# Sheet2.net
KiCad netlist of a schematic drawn in Altium Designer
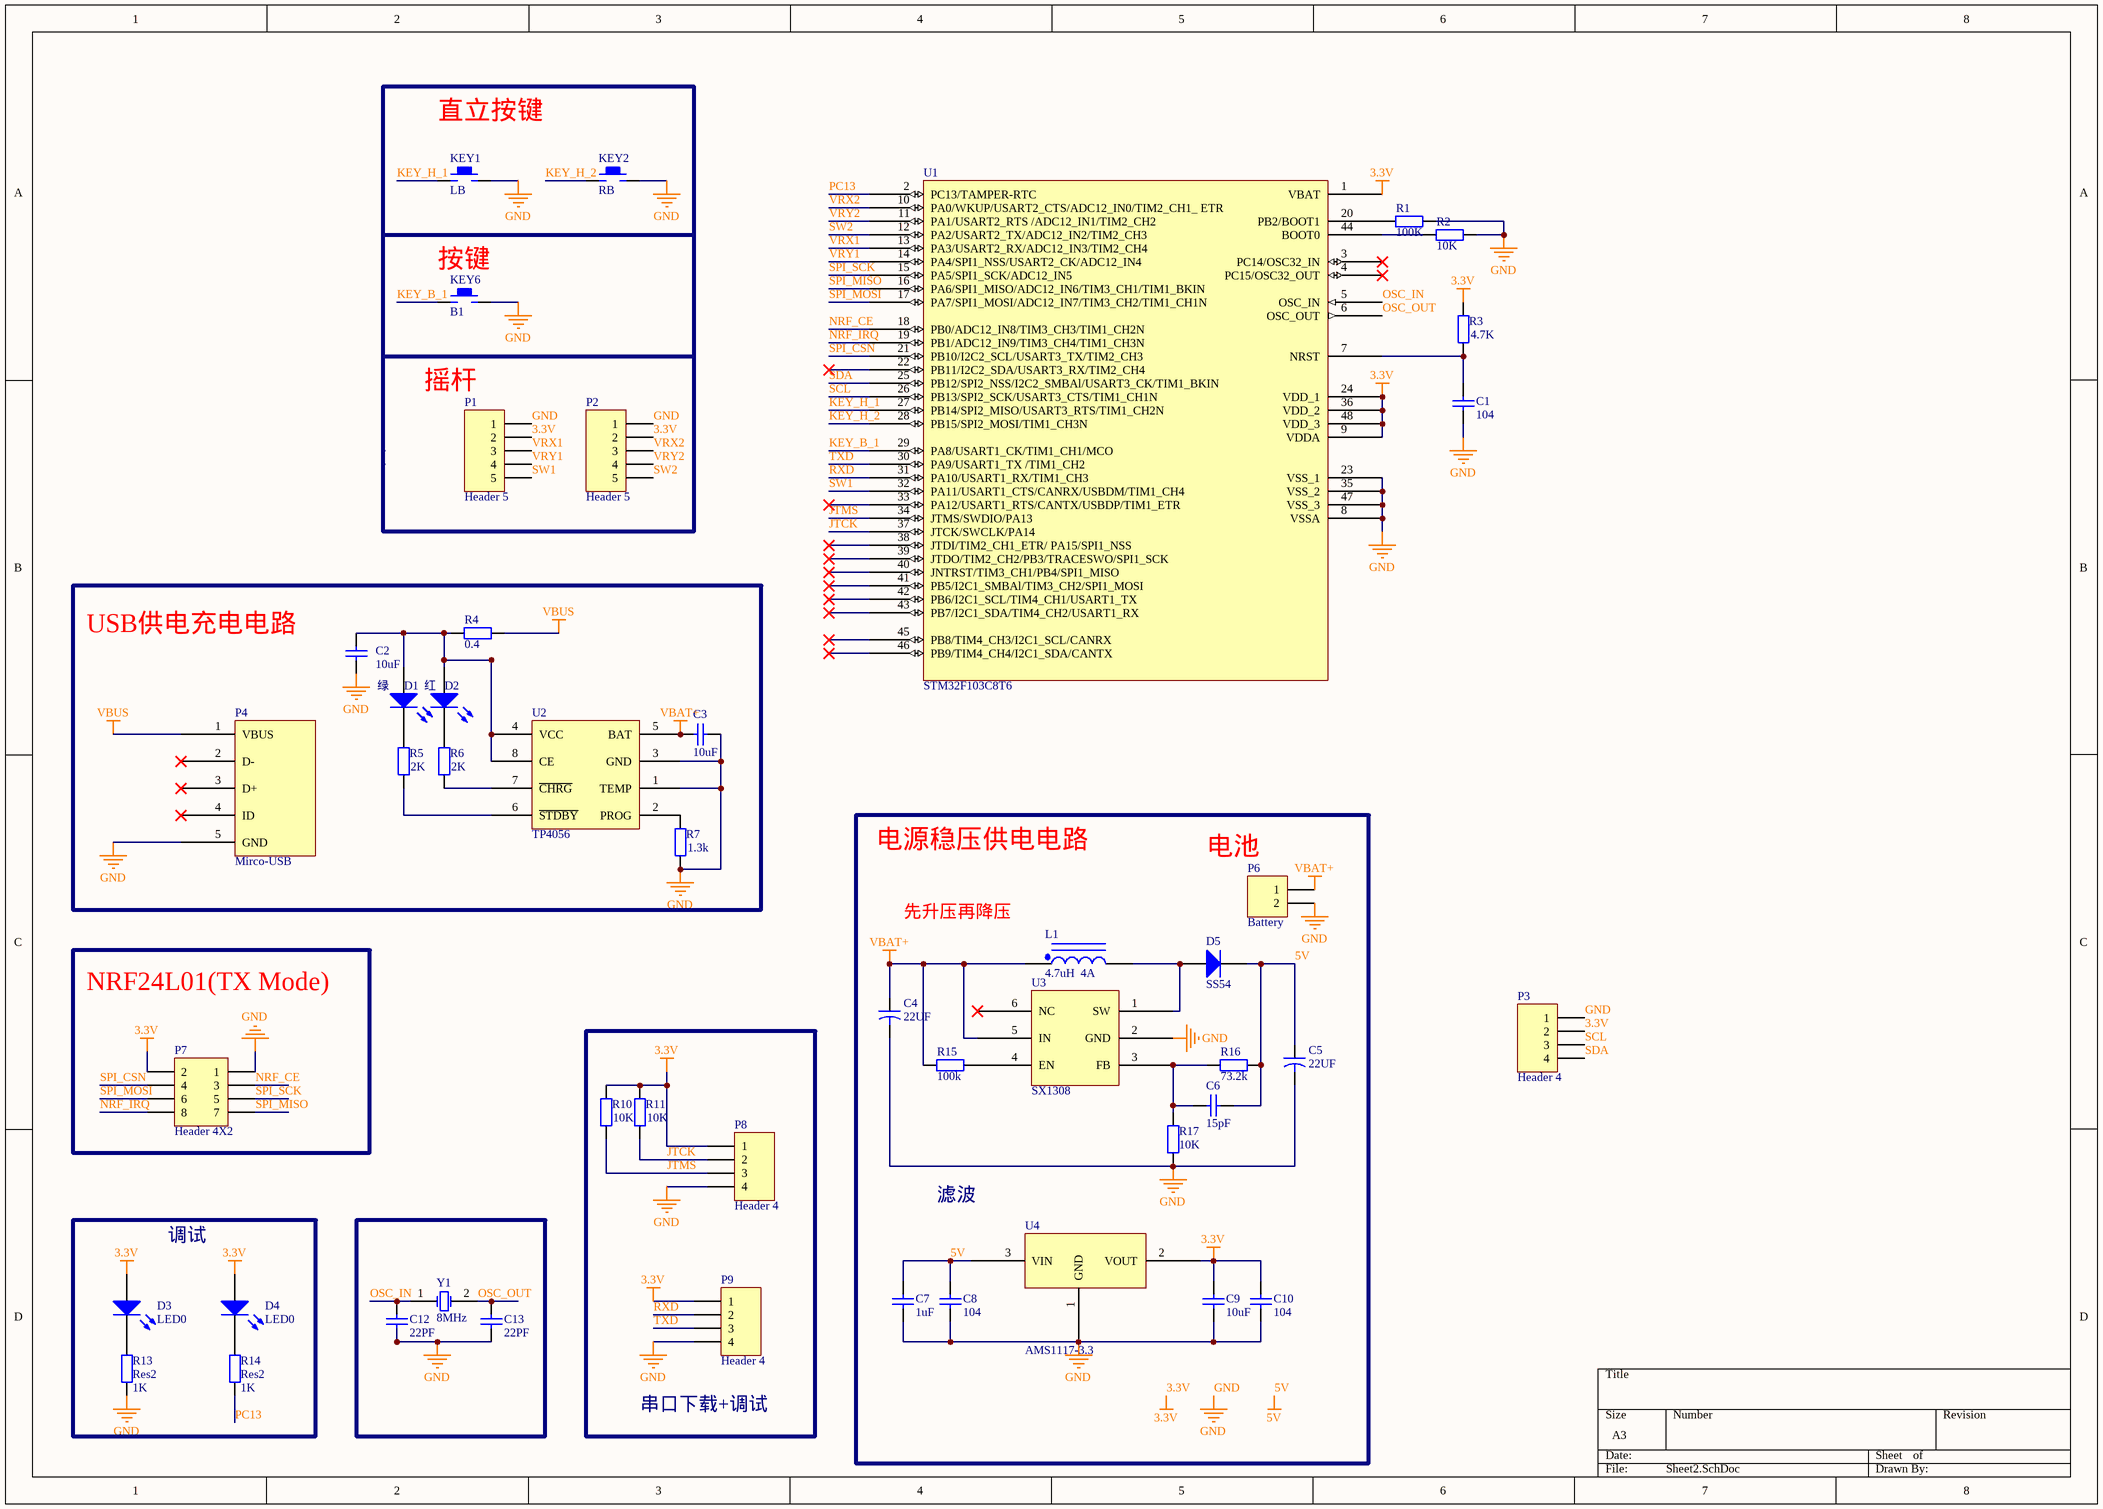
[diagram p0: Sheet2.SchDoc]

(export (version "E")
  (design (tool "Eeschema 10.0.6"))
  (components
    (comp (ref "C1")
      (value "104")
      (footprint "0603")
      (description "Capacitor")
      (fields (field (name "Comment") "Cap") (field (name "PUBLISHER") "Altium Limited"))
      (libsource (lib "Miscellaneous Devices") (part "Cap"))
    )
    (comp (ref "C2")
      (value "10uF")
      (footprint "0603")
      (description "Capacitor")
      (fields (field (name "Comment") "Cap") (field (name "PUBLISHER") "Altium Limited"))
      (libsource (lib "Miscellaneous Devices") (part "Cap"))
    )
    (comp (ref "C3")
      (value "10uF")
      (footprint "0603")
      (description "Capacitor")
      (fields (field (name "Comment") "Cap") (field (name "PUBLISHER") "Altium Limited"))
      (libsource (lib "Miscellaneous Devices") (part "Cap"))
    )
    (comp (ref "C4")
      (value "22UF")
      (footprint "0603")
      (description "Capacitor")
      (fields (field (name "Comment") "Cap2") (field (name "PUBLISHER") "Altium Limited"))
      (libsource (lib "Miscellaneous Devices") (part "Cap2"))
    )
    (comp (ref "C5")
      (value "22UF")
      (footprint "0603")
      (description "Capacitor")
      (fields (field (name "Comment") "Cap2") (field (name "PUBLISHER") "Altium Limited"))
      (libsource (lib "Miscellaneous Devices") (part "Cap2"))
    )
    (comp (ref "C6")
      (value "15pF")
      (footprint "0603")
      (description "Capacitor")
      (fields (field (name "Comment") "Cap") (field (name "PUBLISHER") "Altium Limited"))
      (libsource (lib "Miscellaneous Devices") (part "Cap"))
    )
    (comp (ref "C7")
      (value "1uF")
      (footprint "0603")
      (description "Capacitor")
      (fields (field (name "Comment") "Cap") (field (name "PUBLISHER") "Altium Limited"))
      (libsource (lib "Miscellaneous Devices") (part "Cap"))
    )
    (comp (ref "C8")
      (value "104")
      (footprint "0603")
      (description "Capacitor")
      (fields (field (name "Comment") "Cap") (field (name "PUBLISHER") "Altium Limited"))
      (libsource (lib "Miscellaneous Devices") (part "Cap"))
    )
    (comp (ref "C9")
      (value "10uF")
      (footprint "0603")
      (description "Capacitor")
      (fields (field (name "Comment") "Cap") (field (name "PUBLISHER") "Altium Limited"))
      (libsource (lib "Miscellaneous Devices") (part "Cap"))
    )
    (comp (ref "C10")
      (value "104")
      (footprint "0603")
      (description "Capacitor")
      (fields (field (name "Comment") "Cap") (field (name "PUBLISHER") "Altium Limited"))
      (libsource (lib "Miscellaneous Devices") (part "Cap"))
    )
    (comp (ref "C12")
      (value "22PF")
      (footprint "0603")
      (description "Capacitor")
      (fields (field (name "Comment") "Cap") (field (name "PUBLISHER") "Altium Limited"))
      (libsource (lib "Miscellaneous Devices") (part "Cap"))
    )
    (comp (ref "C13")
      (value "22PF")
      (footprint "0603")
      (description "Capacitor")
      (fields (field (name "Comment") "Cap") (field (name "PUBLISHER") "Altium Limited"))
      (libsource (lib "Miscellaneous Devices") (part "Cap"))
    )
    (comp (ref "D1")
      (value "绿")
      (footprint "0603-LED")
      (description "Typical INFRARED GaAs LED")
      (fields (field (name "PUBLISHER") "Altium Limited"))
      (libsource (lib "Miscellaneous Devices") (part "LED0"))
    )
    (comp (ref "D2")
      (value "红")
      (footprint "0603-LED")
      (description "Typical INFRARED GaAs LED")
      (fields (field (name "PUBLISHER") "Altium Limited"))
      (libsource (lib "Miscellaneous Devices") (part "LED0"))
    )
    (comp (ref "D3")
      (value "LED0")
      (footprint "0603-LED")
      (description "Typical INFRARED GaAs LED")
      (fields (field (name "PUBLISHER") "Altium Limited"))
      (libsource (lib "Miscellaneous Devices") (part "LED0"))
    )
    (comp (ref "D4")
      (value "LED0")
      (footprint "0603-LED")
      (description "Typical INFRARED GaAs LED")
      (fields (field (name "PUBLISHER") "Altium Limited"))
      (libsource (lib "Miscellaneous Devices") (part "LED0"))
    )
    (comp (ref "D5")
      (value "SS54")
      (footprint "DO-214AA/SMB")
      (description "Default Diode")
      (fields (field (name "PUBLISHER") "Altium Limited"))
      (libsource (lib "Miscellaneous Devices") (part "Diode"))
    )
    (comp (ref "KEY1") (value "LB") (footprint "KEY 侧式直插") (libsource (lib "Schlib1") (part "KEY")))
    (comp (ref "KEY2") (value "RB") (footprint "KEY 侧式直插") (libsource (lib "Schlib1") (part "KEY")))
    (comp (ref "KEY6") (value "B1") (footprint "KEY_M") (libsource (lib "Schlib1") (part "KEY")))
    (comp (ref "L1")
      (value "4.7uH  4A")
      (footprint "0603")
      (description "Magnetic-Core Inductor with Winding Polarity Marking")
      (fields (field (name "Comment") "Inductor Iron Dot") (field (name "PUBLISHER") "Altium Limited"))
      (libsource (lib "Miscellaneous Devices") (part "Inductor Iron Dot"))
    )
    (comp (ref "P1")
      (value "Header 5")
      (footprint "摇杆1")
      (description "Header, 5-Pin")
      (fields (field (name "PUBLISHER") "Altium Limited"))
      (libsource (lib "Miscellaneous Connectors") (part "Header 5"))
    )
    (comp (ref "P2")
      (value "Header 5")
      (footprint "摇杆1")
      (description "Header, 5-Pin")
      (fields (field (name "PUBLISHER") "Altium Limited"))
      (libsource (lib "Miscellaneous Connectors") (part "Header 5"))
    )
    (comp (ref "P3")
      (value "Header 4")
      (footprint "HDR1X4")
      (description "Header, 4-Pin")
      (fields (field (name "PUBLISHER") "Altium Limited"))
      (libsource (lib "Miscellaneous Connectors") (part "Header 4"))
    )
    (comp (ref "P4")
      (value "Mirco-USB")
      (footprint "microUSB")
      (description "USB")
      (libsource (lib "Schlib1") (part "Mirco-USB"))
    )
    (comp (ref "P6")
      (value "Battery")
      (footprint "BAT-2")
      (description "Header, 2-Pin")
      (fields (field (name "PUBLISHER") "Altium Limited"))
      (libsource (lib "Miscellaneous Connectors") (part "Header 2"))
    )
    (comp (ref "P7")
      (value "Header 4X2")
      (footprint "HDR2X4")
      (description "Header, 4-Pin, Dual row")
      (fields (field (name "PUBLISHER") "Altium Limited"))
      (libsource (lib "Miscellaneous Connectors") (part "Header 4X2"))
    )
    (comp (ref "P8")
      (value "Header 4")
      (footprint "HDR1X4")
      (description "Header, 4-Pin")
      (fields (field (name "PUBLISHER") "Altium Limited"))
      (libsource (lib "") (part "Header 4_1"))
    )
    (comp (ref "P9")
      (value "Header 4")
      (footprint "HDR1X4")
      (description "Header, 4-Pin")
      (fields (field (name "PUBLISHER") "Altium Limited"))
      (libsource (lib "") (part "Header 4_1"))
    )
    (comp (ref "R1")
      (value "100K")
      (footprint "0603")
      (description "Resistor")
      (fields (field (name "Comment") "Res2") (field (name "PUBLISHER") "Altium Limited"))
      (libsource (lib "Miscellaneous Devices") (part "Res2"))
    )
    (comp (ref "R2")
      (value "10K")
      (footprint "0603")
      (description "Resistor")
      (fields (field (name "Comment") "Res2") (field (name "PUBLISHER") "Altium Limited"))
      (libsource (lib "Miscellaneous Devices") (part "Res2"))
    )
    (comp (ref "R3")
      (value "4.7K")
      (footprint "0603")
      (description "Resistor")
      (fields (field (name "Comment") "Res2") (field (name "PUBLISHER") "Altium Limited"))
      (libsource (lib "") (part "Res2_1"))
    )
    (comp (ref "R4")
      (value "0.4")
      (footprint "0603")
      (description "Resistor")
      (fields (field (name "Comment") "Res2") (field (name "PUBLISHER") "Altium Limited"))
      (libsource (lib "Miscellaneous Devices") (part "Res2"))
    )
    (comp (ref "R5")
      (value "2K")
      (footprint "0603")
      (description "Resistor")
      (fields (field (name "Comment") "Res2") (field (name "PUBLISHER") "Altium Limited"))
      (libsource (lib "") (part "Res2_1"))
    )
    (comp (ref "R6")
      (value "2K")
      (footprint "0603")
      (description "Resistor")
      (fields (field (name "Comment") "Res2") (field (name "PUBLISHER") "Altium Limited"))
      (libsource (lib "") (part "Res2_1"))
    )
    (comp (ref "R7")
      (value "1.3k")
      (footprint "0603")
      (description "Resistor")
      (fields (field (name "Comment") "Res2") (field (name "PUBLISHER") "Altium Limited"))
      (libsource (lib "") (part "Res2_1"))
    )
    (comp (ref "R10")
      (value "10K")
      (footprint "0603")
      (description "Resistor")
      (fields (field (name "Comment") "Res2") (field (name "PUBLISHER") "Altium Limited"))
      (libsource (lib "") (part "Res2_1"))
    )
    (comp (ref "R11")
      (value "10K")
      (footprint "0603")
      (description "Resistor")
      (fields (field (name "Comment") "Res2") (field (name "PUBLISHER") "Altium Limited"))
      (libsource (lib "") (part "Res2_1"))
    )
    (comp (ref "R13")
      (value "Res2")
      (footprint "0603")
      (description "Resistor")
      (fields (field (name "ALTIUM_VALUE") "1K") (field (name "PUBLISHER") "Altium Limited"))
      (libsource (lib "") (part "Res2_1"))
    )
    (comp (ref "R14")
      (value "Res2")
      (footprint "0603")
      (description "Resistor")
      (fields (field (name "ALTIUM_VALUE") "1K") (field (name "PUBLISHER") "Altium Limited"))
      (libsource (lib "") (part "Res2_1"))
    )
    (comp (ref "R15")
      (value "100k")
      (footprint "0603")
      (description "Resistor")
      (fields (field (name "Comment") "Res2") (field (name "PUBLISHER") "Altium Limited"))
      (libsource (lib "Miscellaneous Devices") (part "Res2"))
    )
    (comp (ref "R16")
      (value "73.2k")
      (footprint "0603")
      (description "Resistor")
      (fields (field (name "Comment") "Res2") (field (name "PUBLISHER") "Altium Limited"))
      (libsource (lib "Miscellaneous Devices") (part "Res2"))
    )
    (comp (ref "R17")
      (value "10K")
      (footprint "0603")
      (description "Resistor")
      (fields (field (name "Comment") "Res2") (field (name "PUBLISHER") "Altium Limited"))
      (libsource (lib "") (part "Res2_1"))
    )
    (comp (ref "U1")
      (value "STM32F103C8T6")
      (footprint "LQFP-48")
      (description "ST MCU")
      (libsource (lib "Schlib1") (part "STM32F103C8T6"))
    )
    (comp (ref "U2")
      (value "TP4056")
      (footprint "SOIC-8/SOP-8")
      (description "Battery Charge IC")
      (libsource (lib "Schlib1") (part "TP4056"))
    )
    (comp (ref "U3") (value "SX1308") (footprint "sot-23-6") (libsource (lib "Schlib1") (part "SX1308")))
    (comp (ref "U4")
      (value "AMS1117-3.3")
      (footprint "SOT-223")
      (description "5V->3.3V")
      (libsource (lib "Schlib1") (part "AMS1117-3.3"))
    )
    (comp (ref "Y1")
      (value "8MHz")
      (footprint "LC-HC-49S")
      (description "Crystal Oscillator")
      (fields (field (name "PUBLISHER") "Altium Limited"))
      (libsource (lib "Miscellaneous Devices") (part "XTAL"))
    )
  )
  (nets
    (net (code "1") (name "/JTCK") (class "Default")
      (node (ref "P8") (pin "2") (pinfunction "2_2") (pintype "passive"))
      (node (ref "R11") (pin "1") (pinfunction "1_1") (pintype "passive"))
      (node (ref "U1") (pin "37") (pinfunction "JTCK/SWCLK/PA14_37") (pintype "bidirectional"))
    )
    (net (code "2") (name "/JTMS") (class "Default")
      (node (ref "P8") (pin "3") (pinfunction "3_3") (pintype "passive"))
      (node (ref "R10") (pin "1") (pinfunction "1_1") (pintype "passive"))
      (node (ref "U1") (pin "34") (pinfunction "JTMS/SWDIO/PA13_34") (pintype "bidirectional"))
    )
    (net (code "3") (name "/KEY_B_1") (class "Default")
      (node (ref "KEY6") (pin "1") (pinfunction "1_1") (pintype "passive"))
      (node (ref "U1") (pin "29") (pinfunction "PA8/USART1_CK/TIM1_CH1/MCO_29") (pintype "bidirectional"))
    )
    (net (code "4") (name "/KEY_H_1") (class "Default")
      (node (ref "KEY1") (pin "1") (pinfunction "1_1") (pintype "passive"))
      (node (ref "U1") (pin "27") (pinfunction "PB14/SPI2_MISO/USART3_RTS/TIM1_CH2N_27") (pintype "bidirectional"))
    )
    (net (code "5") (name "/KEY_H_2") (class "Default")
      (node (ref "KEY2") (pin "1") (pinfunction "1_1") (pintype "passive"))
      (node (ref "U1") (pin "28") (pinfunction "PB15/SPI2_MOSI/TIM1_CH3N_28") (pintype "bidirectional"))
    )
    (net (code "6") (name "/NRF_CE") (class "Default")
      (node (ref "P7") (pin "3") (pinfunction "3_3") (pintype "passive"))
      (node (ref "U1") (pin "18") (pinfunction "PB0/ADC12_IN8/TIM3_CH3/TIM1_CH2N_18") (pintype "bidirectional"))
    )
    (net (code "7") (name "/NRF_IRQ") (class "Default")
      (node (ref "P7") (pin "8") (pinfunction "8_8") (pintype "passive"))
      (node (ref "U1") (pin "19") (pinfunction "PB1/ADC12_IN9/TIM3_CH4/TIM1_CH3N_19") (pintype "bidirectional"))
    )
    (net (code "8") (name "/OSC_IN") (class "Default")
      (node (ref "C12") (pin "2") (pinfunction "2_2") (pintype "passive"))
      (node (ref "U1") (pin "5") (pinfunction "OSC_IN_5") (pintype "input"))
      (node (ref "Y1") (pin "1") (pinfunction "OSC1_1") (pintype "passive"))
    )
    (net (code "9") (name "/OSC_OUT") (class "Default")
      (node (ref "C13") (pin "2") (pinfunction "2_2") (pintype "passive"))
      (node (ref "U1") (pin "6") (pinfunction "OSC_OUT_6") (pintype "output"))
      (node (ref "Y1") (pin "2") (pinfunction "OSC2_2") (pintype "passive"))
    )
    (net (code "10") (name "/PC13") (class "Default")
      (node (ref "R14") (pin "1") (pinfunction "1_1") (pintype "passive"))
      (node (ref "U1") (pin "2") (pinfunction "PC13/TAMPER-RTC_2") (pintype "bidirectional"))
    )
    (net (code "11") (name "/RXD") (class "Default")
      (node (ref "P9") (pin "2") (pinfunction "2_2") (pintype "passive"))
      (node (ref "U1") (pin "31") (pinfunction "PA10/USART1_RX/TIM1_CH3_31") (pintype "bidirectional"))
    )
    (net (code "12") (name "/SCL") (class "Default")
      (node (ref "P3") (pin "3") (pinfunction "3_3") (pintype "passive"))
      (node (ref "U1") (pin "26") (pinfunction "PB13/SPI2_SCK/USART3_CTS/TIM1_CH1N_26") (pintype "bidirectional"))
    )
    (net (code "13") (name "/SDA") (class "Default")
      (node (ref "P3") (pin "4") (pinfunction "4_4") (pintype "passive"))
      (node (ref "U1") (pin "25") (pinfunction "PB12/SPI2_NSS/I2C2_SMBAl/USART3_CK/TIM1_BKIN_25") (pintype "bidirectional"))
    )
    (net (code "14") (name "/SPI_CSN") (class "Default")
      (node (ref "P7") (pin "4") (pinfunction "4_4") (pintype "passive"))
      (node (ref "U1") (pin "21") (pinfunction "PB10/I2C2_SCL/USART3_TX/TIM2_CH3_21") (pintype "bidirectional"))
    )
    (net (code "15") (name "/SPI_MISO") (class "Default")
      (node (ref "P7") (pin "7") (pinfunction "7_7") (pintype "passive"))
      (node (ref "U1") (pin "16") (pinfunction "PA6/SPI1_MISO/ADC12_IN6/TIM3_CH1/TIM1_BKIN_16") (pintype "bidirectional"))
    )
    (net (code "16") (name "/SPI_MOSI") (class "Default")
      (node (ref "P7") (pin "6") (pinfunction "6_6") (pintype "passive"))
      (node (ref "U1") (pin "17") (pinfunction "PA7/SPI1_MOSI/ADC12_IN7/TIM3_CH2/TIM1_CH1N_17") (pintype "bidirectional"))
    )
    (net (code "17") (name "/SPI_SCK") (class "Default")
      (node (ref "P7") (pin "5") (pinfunction "5_5") (pintype "passive"))
      (node (ref "U1") (pin "15") (pinfunction "PA5/SPI1_SCK/ADC12_IN5_15") (pintype "bidirectional"))
    )
    (net (code "18") (name "/SW1") (class "Default")
      (node (ref "P1") (pin "5") (pinfunction "5_5") (pintype "passive"))
      (node (ref "U1") (pin "32") (pinfunction "PA11/USART1_CTS/CANRX/USBDM/TIM1_CH4_32") (pintype "bidirectional"))
    )
    (net (code "19") (name "/SW2") (class "Default")
      (node (ref "P2") (pin "5") (pinfunction "5_5") (pintype "passive"))
      (node (ref "U1") (pin "12") (pinfunction "PA2/USART2_TX/ADC12_IN2/TIM2_CH3_12") (pintype "bidirectional"))
    )
    (net (code "20") (name "/TXD") (class "Default")
      (node (ref "P9") (pin "3") (pinfunction "3_3") (pintype "passive"))
      (node (ref "U1") (pin "30") (pinfunction "PA9/USART1_TX_/TIM1_CH2_30") (pintype "bidirectional"))
    )
    (net (code "21") (name "/VRX1") (class "Default")
      (node (ref "P1") (pin "3") (pinfunction "3_3") (pintype "passive"))
      (node (ref "U1") (pin "13") (pinfunction "PA3/USART2_RX/ADC12_IN3/TIM2_CH4_13") (pintype "bidirectional"))
    )
    (net (code "22") (name "/VRX2") (class "Default")
      (node (ref "P2") (pin "3") (pinfunction "3_3") (pintype "passive"))
      (node (ref "U1") (pin "10") (pinfunction "PA0/WKUP/USART2_CTS/ADC12_IN0/TIM2_CH1__ETR_10") (pintype "bidirectional"))
    )
    (net (code "23") (name "/VRY1") (class "Default")
      (node (ref "P1") (pin "4") (pinfunction "4_4") (pintype "passive"))
      (node (ref "U1") (pin "14") (pinfunction "PA4/SPI1_NSS/USART2_CK/ADC12_IN4_14") (pintype "bidirectional"))
    )
    (net (code "24") (name "/VRY2") (class "Default")
      (node (ref "P2") (pin "4") (pinfunction "4_4") (pintype "passive"))
      (node (ref "U1") (pin "11") (pinfunction "PA1/USART2_RTS_/ADC12_IN1/TIM2_CH2_11") (pintype "bidirectional"))
    )
    (net (code "25") (name "3.3V") (class "Default")
      (node (ref "C10") (pin "2") (pinfunction "2_2") (pintype "passive"))
      (node (ref "C9") (pin "2") (pinfunction "2_2") (pintype "passive"))
      (node (ref "D3") (pin "1") (pinfunction "A_1") (pintype "passive"))
      (node (ref "D4") (pin "1") (pinfunction "A_1") (pintype "passive"))
      (node (ref "P1") (pin "2") (pinfunction "2_2") (pintype "passive"))
      (node (ref "P2") (pin "2") (pinfunction "2_2") (pintype "passive"))
      (node (ref "P3") (pin "2") (pinfunction "2_2") (pintype "passive"))
      (node (ref "P7") (pin "2") (pinfunction "2_2") (pintype "passive"))
      (node (ref "P8") (pin "1") (pinfunction "1_1") (pintype "passive"))
      (node (ref "P9") (pin "1") (pinfunction "1_1") (pintype "passive"))
      (node (ref "R10") (pin "2") (pinfunction "2_2") (pintype "passive"))
      (node (ref "R11") (pin "2") (pinfunction "2_2") (pintype "passive"))
      (node (ref "R3") (pin "2") (pinfunction "2_2") (pintype "passive"))
      (node (ref "U1") (pin "1") (pinfunction "VBAT_1") (pintype "power_in"))
      (node (ref "U1") (pin "24") (pinfunction "VDD_1_24") (pintype "power_in"))
      (node (ref "U1") (pin "36") (pinfunction "VDD_2_36") (pintype "power_in"))
      (node (ref "U1") (pin "48") (pinfunction "VDD_3_48") (pintype "power_in"))
      (node (ref "U1") (pin "9") (pinfunction "VDDA_9") (pintype "power_in"))
      (node (ref "U4") (pin "2") (pinfunction "VOUT_2") (pintype "power_in"))
    )
    (net (code "26") (name "5V") (class "Default")
      (node (ref "C5") (pin "1") (pinfunction "1_1") (pintype "passive"))
      (node (ref "C6") (pin "1") (pinfunction "1_1") (pintype "passive"))
      (node (ref "C7") (pin "2") (pinfunction "2_2") (pintype "passive"))
      (node (ref "C8") (pin "2") (pinfunction "2_2") (pintype "passive"))
      (node (ref "D5") (pin "2") (pinfunction "K_2") (pintype "passive"))
      (node (ref "R16") (pin "1") (pinfunction "1_1") (pintype "passive"))
      (node (ref "U4") (pin "3") (pinfunction "VIN_3") (pintype "power_in"))
    )
    (net (code "27") (name "GND") (class "Default")
      (node (ref "C1") (pin "1") (pinfunction "1_1") (pintype "passive"))
      (node (ref "C10") (pin "1") (pinfunction "1_1") (pintype "passive"))
      (node (ref "C12") (pin "1") (pinfunction "1_1") (pintype "passive"))
      (node (ref "C13") (pin "1") (pinfunction "1_1") (pintype "passive"))
      (node (ref "C2") (pin "1") (pinfunction "1_1") (pintype "passive"))
      (node (ref "C3") (pin "2") (pinfunction "2_2") (pintype "passive"))
      (node (ref "C4") (pin "2") (pinfunction "2_2") (pintype "passive"))
      (node (ref "C5") (pin "2") (pinfunction "2_2") (pintype "passive"))
      (node (ref "C7") (pin "1") (pinfunction "1_1") (pintype "passive"))
      (node (ref "C8") (pin "1") (pinfunction "1_1") (pintype "passive"))
      (node (ref "C9") (pin "1") (pinfunction "1_1") (pintype "passive"))
      (node (ref "KEY1") (pin "2") (pinfunction "2_2") (pintype "passive"))
      (node (ref "KEY2") (pin "2") (pinfunction "2_2") (pintype "passive"))
      (node (ref "KEY6") (pin "2") (pinfunction "2_2") (pintype "passive"))
      (node (ref "P1") (pin "1") (pinfunction "1_1") (pintype "passive"))
      (node (ref "P2") (pin "1") (pinfunction "1_1") (pintype "passive"))
      (node (ref "P3") (pin "1") (pinfunction "1_1") (pintype "passive"))
      (node (ref "P4") (pin "5") (pinfunction "GND_5") (pintype "passive"))
      (node (ref "P6") (pin "2") (pinfunction "2_2") (pintype "passive"))
      (node (ref "P7") (pin "1") (pinfunction "1_1") (pintype "passive"))
      (node (ref "P8") (pin "4") (pinfunction "4_4") (pintype "passive"))
      (node (ref "P9") (pin "4") (pinfunction "4_4") (pintype "passive"))
      (node (ref "R1") (pin "1") (pinfunction "1_1") (pintype "passive"))
      (node (ref "R13") (pin "1") (pinfunction "1_1") (pintype "passive"))
      (node (ref "R17") (pin "1") (pinfunction "1_1") (pintype "passive"))
      (node (ref "R2") (pin "1") (pinfunction "1_1") (pintype "passive"))
      (node (ref "R7") (pin "1") (pinfunction "1_1") (pintype "passive"))
      (node (ref "U1") (pin "23") (pinfunction "VSS_1_23") (pintype "power_in"))
      (node (ref "U1") (pin "35") (pinfunction "VSS_2_35") (pintype "power_in"))
      (node (ref "U1") (pin "47") (pinfunction "VSS_3_47") (pintype "power_in"))
      (node (ref "U1") (pin "8") (pinfunction "VSSA_8") (pintype "power_in"))
      (node (ref "U2") (pin "1") (pinfunction "TEMP_1") (pintype "passive"))
      (node (ref "U2") (pin "3") (pinfunction "GND_3") (pintype "passive"))
      (node (ref "U3") (pin "2") (pinfunction "GND_2") (pintype "power_in"))
      (node (ref "U4") (pin "1") (pinfunction "GND_1") (pintype "power_in"))
    )
    (net (code "28") (name "Net-(D1-A)") (class "Default")
      (node (ref "C2") (pin "2") (pinfunction "2_2") (pintype "passive"))
      (node (ref "D1") (pin "1") (pinfunction "A_1") (pintype "passive"))
      (node (ref "D2") (pin "1") (pinfunction "A_1") (pintype "passive"))
      (node (ref "R4") (pin "2") (pinfunction "2_2") (pintype "passive"))
      (node (ref "U2") (pin "4") (pinfunction "VCC_4") (pintype "passive"))
      (node (ref "U2") (pin "8") (pinfunction "CE_8") (pintype "passive"))
    )
    (net (code "29") (name "Net-(D1-K)") (class "Default")
      (node (ref "D1") (pin "2") (pinfunction "K_2") (pintype "passive"))
      (node (ref "R5") (pin "2") (pinfunction "2_2") (pintype "passive"))
    )
    (net (code "30") (name "Net-(D2-K)") (class "Default")
      (node (ref "D2") (pin "2") (pinfunction "K_2") (pintype "passive"))
      (node (ref "R6") (pin "2") (pinfunction "2_2") (pintype "passive"))
    )
    (net (code "31") (name "Net-(D3-K)") (class "Default")
      (node (ref "D3") (pin "2") (pinfunction "K_2") (pintype "passive"))
      (node (ref "R13") (pin "2") (pinfunction "2_2") (pintype "passive"))
    )
    (net (code "32") (name "Net-(D4-K)") (class "Default")
      (node (ref "D4") (pin "2") (pinfunction "K_2") (pintype "passive"))
      (node (ref "R14") (pin "2") (pinfunction "2_2") (pintype "passive"))
    )
    (net (code "33") (name "Net-(D5-A)") (class "Default")
      (node (ref "D5") (pin "1") (pinfunction "A_1") (pintype "passive"))
      (node (ref "L1") (pin "2") (pinfunction "2_2") (pintype "passive"))
      (node (ref "U3") (pin "1") (pinfunction "SW_1") (pintype "passive"))
    )
    (net (code "34") (name "Net-(U1-BOOT0)") (class "Default")
      (node (ref "R2") (pin "2") (pinfunction "2_2") (pintype "passive"))
      (node (ref "U1") (pin "44") (pinfunction "BOOT0_44") (pintype "passive"))
    )
    (net (code "35") (name "Net-(U1-NRST)") (class "Default")
      (node (ref "C1") (pin "2") (pinfunction "2_2") (pintype "passive"))
      (node (ref "R3") (pin "1") (pinfunction "1_1") (pintype "passive"))
      (node (ref "U1") (pin "7") (pinfunction "NRST_7") (pintype "passive"))
    )
    (net (code "36") (name "Net-(U1-PB2{slash}BOOT1)") (class "Default")
      (node (ref "R1") (pin "2") (pinfunction "2_2") (pintype "passive"))
      (node (ref "U1") (pin "20") (pinfunction "PB2/BOOT1_20") (pintype "passive"))
    )
    (net (code "37") (name "Net-(U2-PROG)") (class "Default")
      (node (ref "R7") (pin "2") (pinfunction "2_2") (pintype "passive"))
      (node (ref "U2") (pin "2") (pinfunction "PROG_2") (pintype "passive"))
    )
    (net (code "38") (name "Net-(U2-~{CHRG})") (class "Default")
      (node (ref "R6") (pin "1") (pinfunction "1_1") (pintype "passive"))
      (node (ref "U2") (pin "7") (pinfunction "~{CHRG}_7") (pintype "passive"))
    )
    (net (code "39") (name "Net-(U2-~{STDBY})") (class "Default")
      (node (ref "R5") (pin "1") (pinfunction "1_1") (pintype "passive"))
      (node (ref "U2") (pin "6") (pinfunction "~{STDBY}_6") (pintype "passive"))
    )
    (net (code "40") (name "Net-(U3-EN)") (class "Default")
      (node (ref "R15") (pin "1") (pinfunction "1_1") (pintype "passive"))
      (node (ref "U3") (pin "4") (pinfunction "EN_4") (pintype "passive"))
    )
    (net (code "41") (name "Net-(U3-FB)") (class "Default")
      (node (ref "C6") (pin "2") (pinfunction "2_2") (pintype "passive"))
      (node (ref "R16") (pin "2") (pinfunction "2_2") (pintype "passive"))
      (node (ref "R17") (pin "2") (pinfunction "2_2") (pintype "passive"))
      (node (ref "U3") (pin "3") (pinfunction "FB_3") (pintype "passive"))
    )
    (net (code "42") (name "VBAT+") (class "Default")
      (node (ref "C3") (pin "1") (pinfunction "1_1") (pintype "passive"))
      (node (ref "C4") (pin "1") (pinfunction "1_1") (pintype "passive"))
      (node (ref "L1") (pin "1") (pinfunction "1_1") (pintype "passive"))
      (node (ref "P6") (pin "1") (pinfunction "1_1") (pintype "passive"))
      (node (ref "R15") (pin "2") (pinfunction "2_2") (pintype "passive"))
      (node (ref "U2") (pin "5") (pinfunction "BAT_5") (pintype "passive"))
      (node (ref "U3") (pin "5") (pinfunction "IN_5") (pintype "power_in"))
    )
    (net (code "43") (name "VBUS") (class "Default")
      (node (ref "P4") (pin "1") (pinfunction "VBUS_1") (pintype "power_in"))
      (node (ref "R4") (pin "1") (pinfunction "1_1") (pintype "passive"))
    )
    (net (code "44") (name "unconnected-(P4-D+-Pad3)") (class "Default")
      (node (ref "P4") (pin "3") (pinfunction "D+_3") (pintype "passive+no_connect"))
    )
    (net (code "45") (name "unconnected-(P4-D--Pad2)") (class "Default")
      (node (ref "P4") (pin "2") (pinfunction "D-_2") (pintype "passive+no_connect"))
    )
    (net (code "46") (name "unconnected-(P4-ID-Pad4)") (class "Default")
      (node (ref "P4") (pin "4") (pinfunction "ID_4") (pintype "passive+no_connect"))
    )
    (net (code "47") (name "unconnected-(U1-JNTRST{slash}TIM3_CH1{slash}PB4{slash}SPI1_MISO-Pad40)") (class "Default")
      (node (ref "U1") (pin "40") (pinfunction "JNTRST/TIM3_CH1/PB4/SPI1_MISO_40") (pintype "bidirectional+no_connect"))
    )
    (net (code "48") (name "unconnected-(U1-JTDI{slash}TIM2_CH1_ETR{slash}_PA15{slash}SPI1_NSS-Pad38)") (class "Default")
      (node (ref "U1") (pin "38") (pinfunction "JTDI/TIM2_CH1_ETR/_PA15/SPI1_NSS_38") (pintype "bidirectional+no_connect"))
    )
    (net (code "49") (name "unconnected-(U1-JTDO{slash}TIM2_CH2{slash}PB3{slash}TRACESWO{slash}SPI1_SCK-Pad39)") (class "Default")
      (node (ref "U1") (pin "39") (pinfunction "JTDO/TIM2_CH2/PB3/TRACESWO/SPI1_SCK_39") (pintype "bidirectional+no_connect"))
    )
    (net (code "50") (name "unconnected-(U1-PA12{slash}USART1_RTS{slash}CANTX{slash}USBDP{slash}TIM1_ETR-Pad33)") (class "Default")
      (node (ref "U1") (pin "33") (pinfunction "PA12/USART1_RTS/CANTX/USBDP/TIM1_ETR_33") (pintype "bidirectional+no_connect"))
    )
    (net (code "51") (name "unconnected-(U1-PB5{slash}I2C1_SMBAl{slash}TIM3_CH2{slash}SPI1_MOSI-Pad41)") (class "Default")
      (node (ref "U1") (pin "41") (pinfunction "PB5/I2C1_SMBAl/TIM3_CH2/SPI1_MOSI_41") (pintype "bidirectional+no_connect"))
    )
    (net (code "52") (name "unconnected-(U1-PB6{slash}I2C1_SCL{slash}TIM4_CH1{slash}USART1_TX-Pad42)") (class "Default")
      (node (ref "U1") (pin "42") (pinfunction "PB6/I2C1_SCL/TIM4_CH1/USART1_TX_42") (pintype "bidirectional+no_connect"))
    )
    (net (code "53") (name "unconnected-(U1-PB7{slash}I2C1_SDA{slash}TIM4_CH2{slash}USART1_RX-Pad43)") (class "Default")
      (node (ref "U1") (pin "43") (pinfunction "PB7/I2C1_SDA/TIM4_CH2/USART1_RX_43") (pintype "bidirectional+no_connect"))
    )
    (net (code "54") (name "unconnected-(U1-PB8{slash}TIM4_CH3{slash}I2C1_SCL{slash}CANRX-Pad45)") (class "Default")
      (node (ref "U1") (pin "45") (pinfunction "PB8/TIM4_CH3/I2C1_SCL/CANRX_45") (pintype "bidirectional+no_connect"))
    )
    (net (code "55") (name "unconnected-(U1-PB9{slash}TIM4_CH4{slash}I2C1_SDA{slash}CANTX-Pad46)") (class "Default")
      (node (ref "U1") (pin "46") (pinfunction "PB9/TIM4_CH4/I2C1_SDA/CANTX_46") (pintype "bidirectional+no_connect"))
    )
    (net (code "56") (name "unconnected-(U1-PB11{slash}I2C2_SDA{slash}USART3_RX{slash}TIM2_CH4-Pad22)") (class "Default")
      (node (ref "U1") (pin "22") (pinfunction "PB11/I2C2_SDA/USART3_RX/TIM2_CH4_22") (pintype "bidirectional+no_connect"))
    )
    (net (code "57") (name "unconnected-(U1-PC14{slash}OSC32_IN-Pad3)") (class "Default")
      (node (ref "U1") (pin "3") (pinfunction "PC14/OSC32_IN_3") (pintype "bidirectional+no_connect"))
    )
    (net (code "58") (name "unconnected-(U1-PC15{slash}OSC32_OUT-Pad4)") (class "Default")
      (node (ref "U1") (pin "4") (pinfunction "PC15/OSC32_OUT_4") (pintype "bidirectional+no_connect"))
    )
    (net (code "59") (name "unconnected-(U3-NC-Pad6)") (class "Default")
      (node (ref "U3") (pin "6") (pinfunction "NC_6") (pintype "power_in+no_connect"))
    )
  )
)
